# ShengLiBan_v1_0.net
KiCad netlist of a schematic drawn in EasyEDA Pro
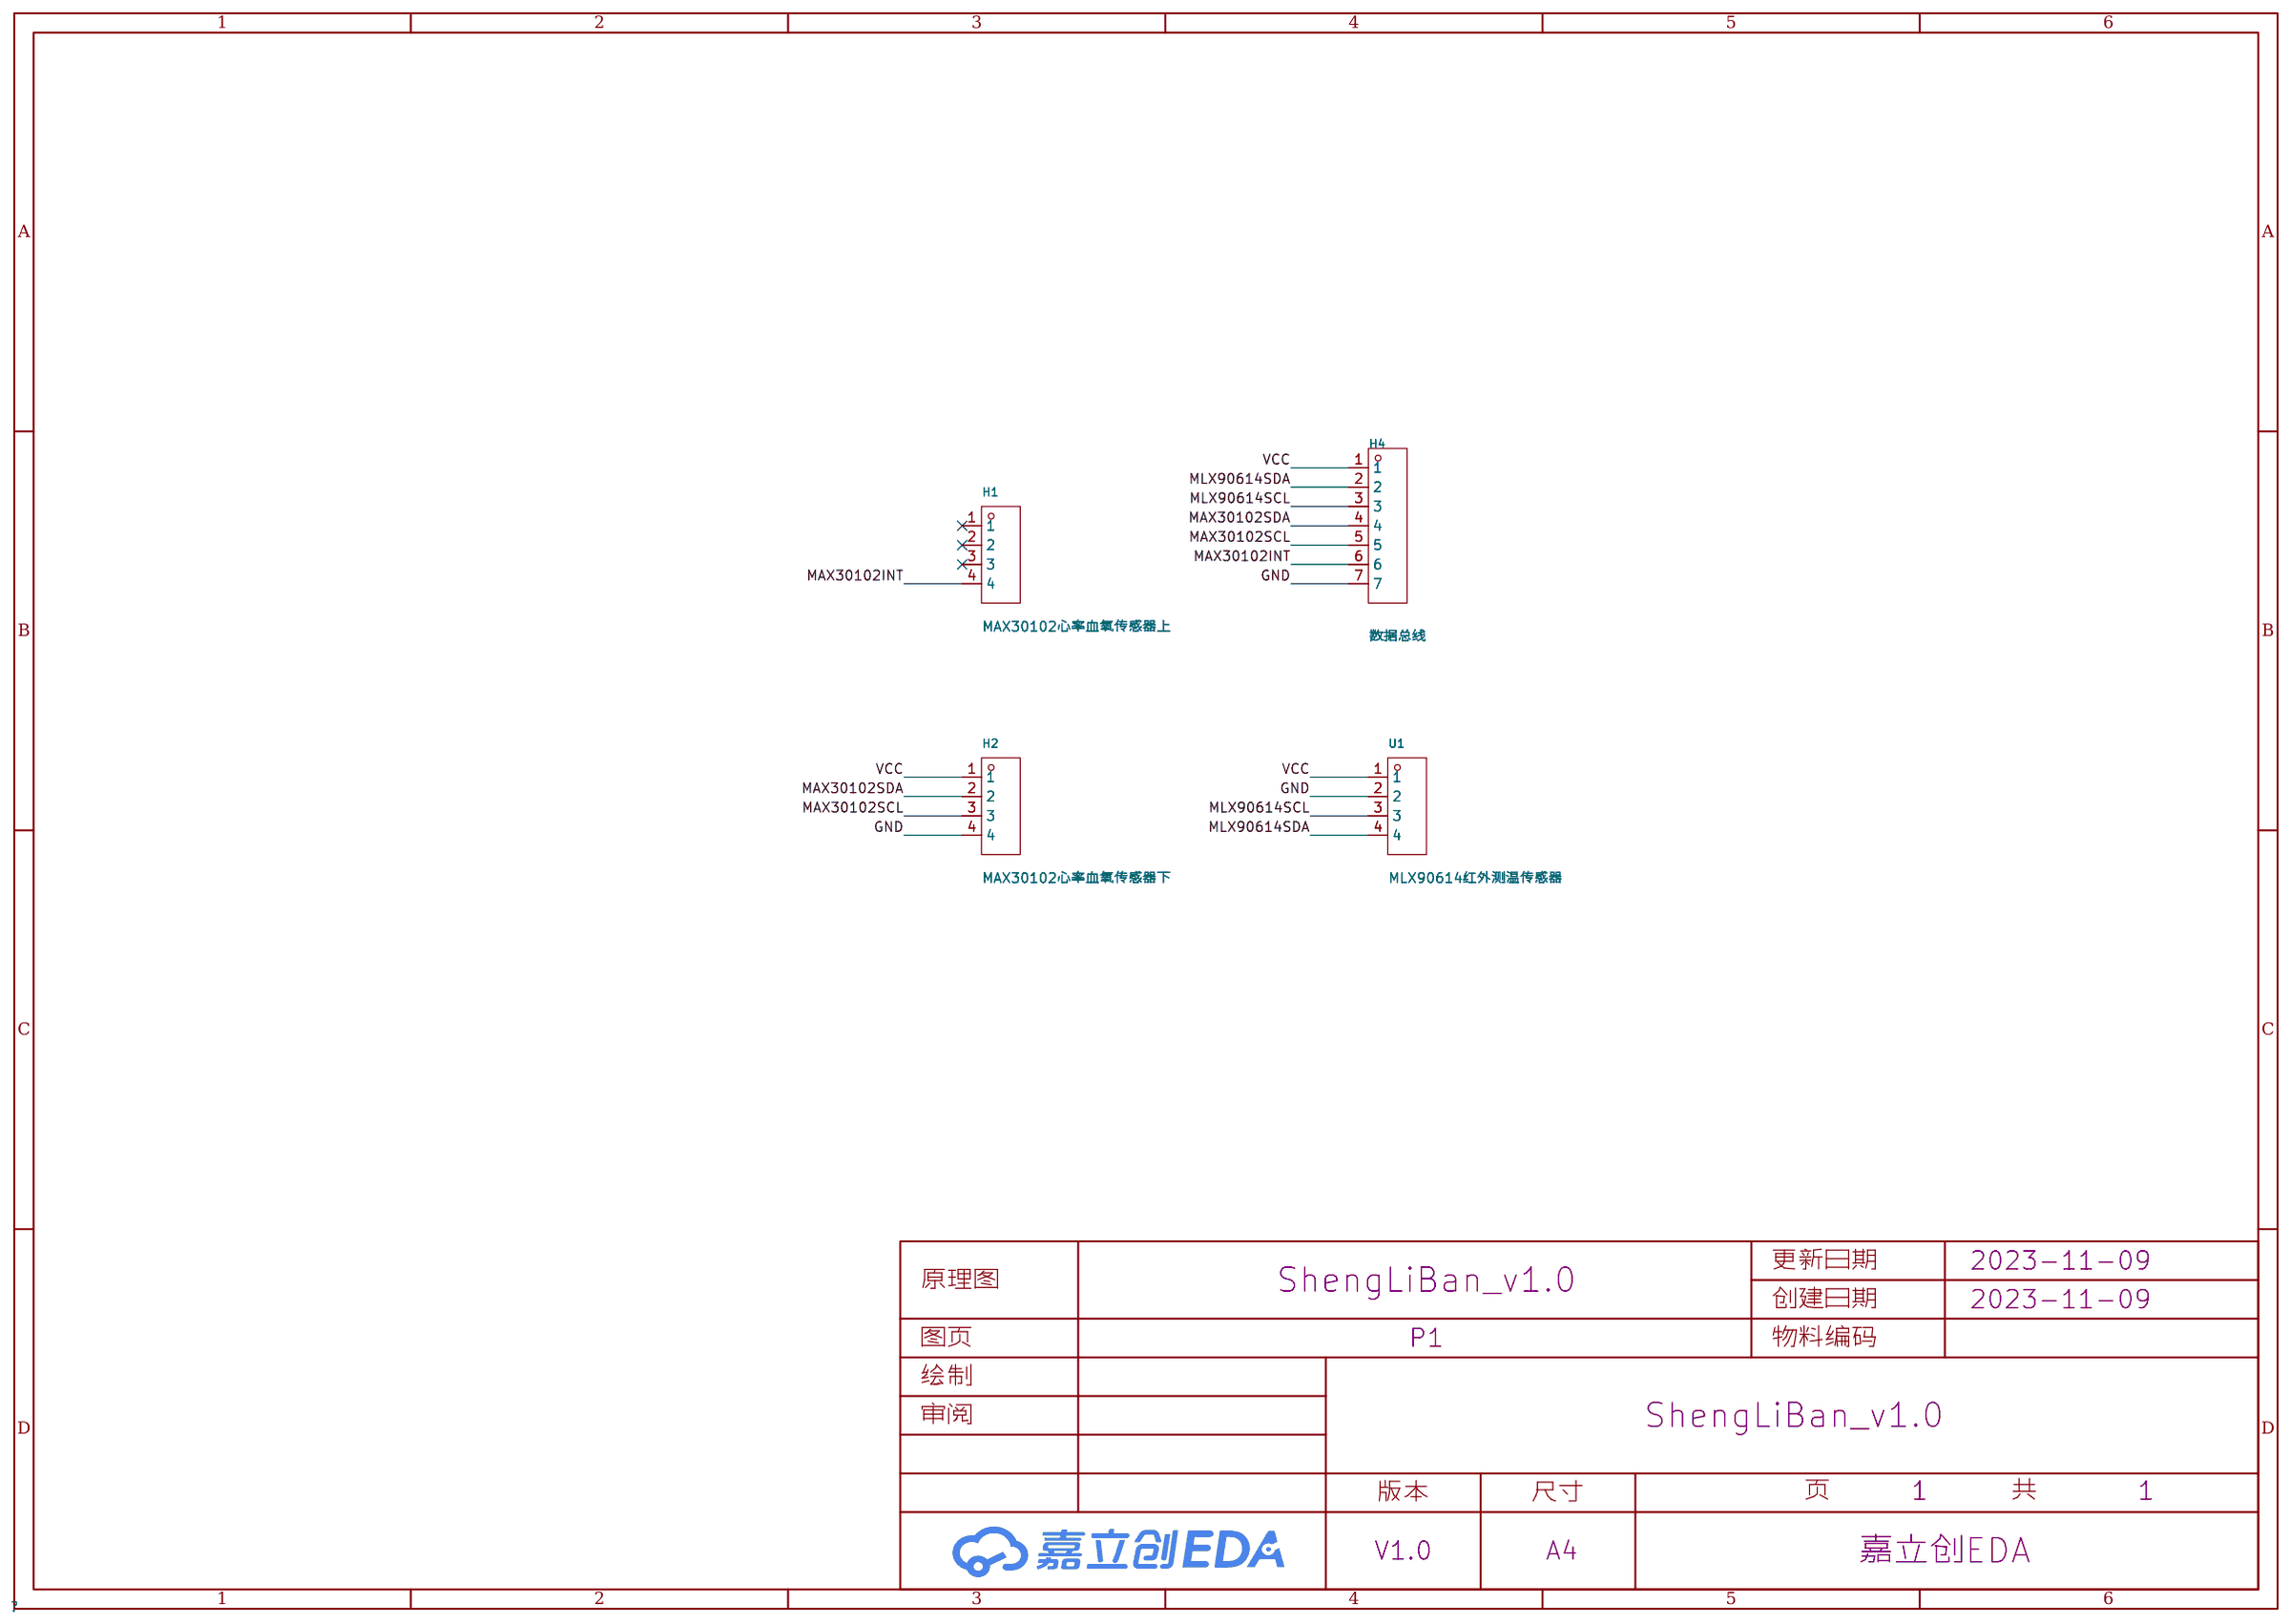
[diagram p0: schematic sheet]

(export (version "E")
  (design (tool "Eeschema 10.0.6"))
  (components
    (comp (ref "H1")
      (value "MAX30102心率血氧传感器上")
      (footprint "easyedapro:HDR-TH_4P-P2.54-V-M")
      (fields (field (name "Manufacturer") "XFCN(兴飞)"))
      (libsource (lib "easyedapro") (part "PZ254V-11-04P_C2691448"))
    )
    (comp (ref "H2")
      (value "MAX30102心率血氧传感器下")
      (footprint "easyedapro:HDR-TH_4P-P2.54-V-M")
      (fields (field (name "Manufacturer") "XFCN(兴飞)"))
      (libsource (lib "easyedapro") (part "PZ254V-11-04P_C2691448"))
    )
    (comp (ref "H4")
      (value "数据总线")
      (footprint "easyedapro:HDR-TH_7P-P2.54-V-M")
      (fields (field (name "Manufacturer") "XFCN(兴飞)"))
      (libsource (lib "easyedapro") (part "PZ254V-11-07P"))
    )
    (comp (ref "U1")
      (value "MLX90614红外测温传感器")
      (footprint "easyedapro:HDR-TH_4P-P2.54-H-F-W10.0-N")
      (fields (field (name "Manufacturer") "HCTL(华灿天禄)"))
      (libsource (lib "easyedapro") (part "PM254-1-04-W-8.5"))
    )
  )
  (nets
    (net (code "1") (name "/GND") (class "Default")
      (node (ref "H2") (pin "4") (pinfunction "4_4") (pintype "input"))
      (node (ref "H4") (pin "7") (pinfunction "7_7") (pintype "input"))
      (node (ref "U1") (pin "2") (pinfunction "2_2") (pintype "input"))
    )
    (net (code "2") (name "/MAX30102INT") (class "Default")
      (node (ref "H1") (pin "4") (pinfunction "4_4") (pintype "input"))
      (node (ref "H4") (pin "6") (pinfunction "6_6") (pintype "input"))
    )
    (net (code "3") (name "/MAX30102SCL") (class "Default")
      (node (ref "H2") (pin "3") (pinfunction "3_3") (pintype "input"))
      (node (ref "H4") (pin "5") (pinfunction "5_5") (pintype "input"))
    )
    (net (code "4") (name "/MAX30102SDA") (class "Default")
      (node (ref "H2") (pin "2") (pinfunction "2_2") (pintype "input"))
      (node (ref "H4") (pin "4") (pinfunction "4_4") (pintype "input"))
    )
    (net (code "5") (name "/MLX90614SCL") (class "Default")
      (node (ref "H4") (pin "3") (pinfunction "3_3") (pintype "input"))
      (node (ref "U1") (pin "3") (pinfunction "3_3") (pintype "input"))
    )
    (net (code "6") (name "/MLX90614SDA") (class "Default")
      (node (ref "H4") (pin "2") (pinfunction "2_2") (pintype "input"))
      (node (ref "U1") (pin "4") (pinfunction "4_4") (pintype "input"))
    )
    (net (code "7") (name "/VCC") (class "Default")
      (node (ref "H2") (pin "1") (pinfunction "1_1") (pintype "input"))
      (node (ref "H4") (pin "1") (pinfunction "1_1") (pintype "input"))
      (node (ref "U1") (pin "1") (pinfunction "1_1") (pintype "input"))
    )
    (net (code "8") (name "unconnected-(H1-Pad1)") (class "Default")
      (node (ref "H1") (pin "1") (pinfunction "1_1") (pintype "input+no_connect"))
    )
    (net (code "9") (name "unconnected-(H1-Pad2)") (class "Default")
      (node (ref "H1") (pin "2") (pinfunction "2_2") (pintype "input+no_connect"))
    )
    (net (code "10") (name "unconnected-(H1-Pad3)") (class "Default")
      (node (ref "H1") (pin "3") (pinfunction "3_3") (pintype "input+no_connect"))
    )
  )
)
